# hotair.net
KiCad netlist of a schematic drawn in Altium Designer
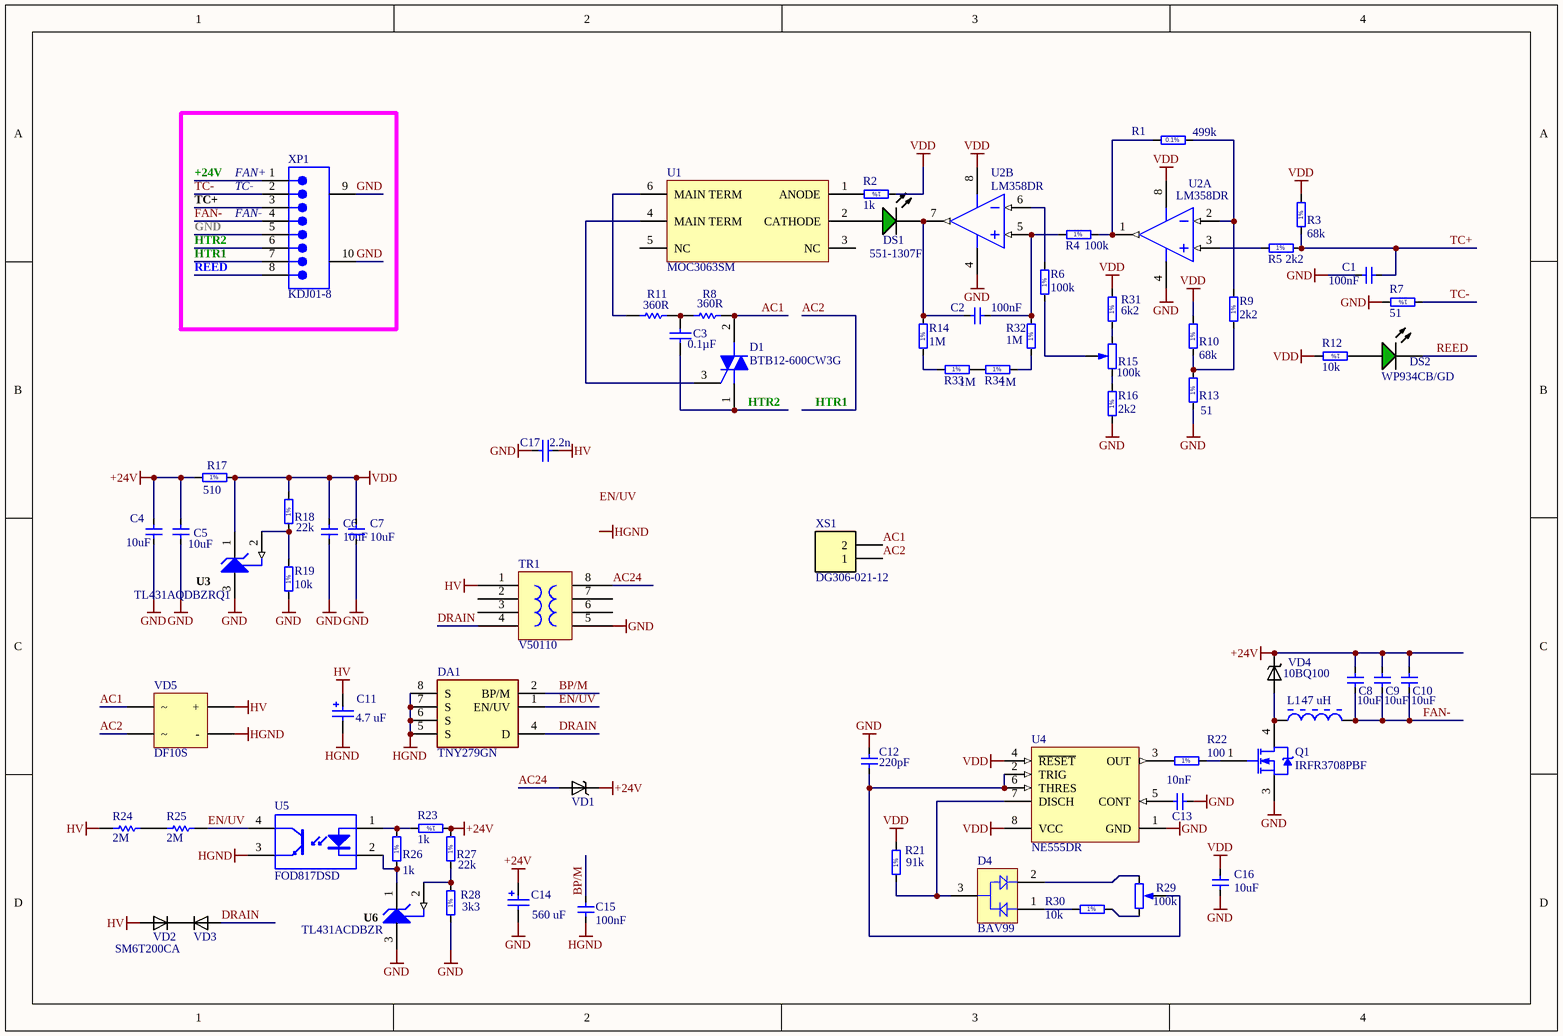
[diagram p0: hotair.SchDoc]

(export (version "E")
  (design (tool "Eeschema 10.0.6"))
  (components
    (comp (ref "C1")
      (value "100nF")
      (footprint "CAP0805R")
      (fields
        (field (name "PART NUMBER") "CC0805_100NF_50V_10%_X7R")
        (field (name "VOLTAGE") "50V")
        (field (name "TOLERANCE") "±10%")
        (field (name "AUTHOR") "I. Kuznetsov")
      )
      (libsource (lib "Capacitor") (part "CAP_NON_POLAR"))
    )
    (comp (ref "C2")
      (value "100nF")
      (footprint "CAP0805R")
      (fields
        (field (name "PART NUMBER") "CC0805_100NF_50V_10%_X7R")
        (field (name "VOLTAGE") "50V")
        (field (name "TOLERANCE") "±10%")
        (field (name "AUTHOR") "I. Kuznetsov")
      )
      (libsource (lib "Capacitor") (part "CAP_NON_POLAR"))
    )
    (comp (ref "C3")
      (value "A104M15X7RF5TAA")
      (footprint "CAPA55-380X260")
      (fields
        (field (name "MANUFACTURER") "Vishay")
        (field (name "CAPACITANCE") "0.1µF")
        (field (name "TOLERANCE") "±20%")
      )
      (libsource (lib "Altium Content Vault") (part "CAP-NP-2"))
    )
    (comp (ref "C4")
      (value "10uF")
      (footprint "CAP0805R")
      (fields
        (field (name "PART NUMBER") "CC0805_10UF_25V_10%_X5R")
        (field (name "VOLTAGE") "25V")
        (field (name "TOLERANCE") "±10%")
        (field (name "AUTHOR") "I. Kuznetsov")
      )
      (libsource (lib "Capacitor") (part "CAP_NON_POLAR"))
    )
    (comp (ref "C5")
      (value "10uF")
      (footprint "CAP0805R")
      (fields
        (field (name "PART NUMBER") "CC0805_10UF_25V_10%_X5R")
        (field (name "VOLTAGE") "25V")
        (field (name "TOLERANCE") "±10%")
        (field (name "AUTHOR") "I. Kuznetsov")
      )
      (libsource (lib "Capacitor") (part "CAP_NON_POLAR"))
    )
    (comp (ref "C6")
      (value "10uF")
      (footprint "CAP0805R")
      (fields
        (field (name "PART NUMBER") "CC0805_10UF_25V_10%_X5R")
        (field (name "VOLTAGE") "25V")
        (field (name "TOLERANCE") "±10%")
        (field (name "AUTHOR") "I. Kuznetsov")
      )
      (libsource (lib "Capacitor") (part "CAP_NON_POLAR"))
    )
    (comp (ref "C7")
      (value "10uF")
      (footprint "CAP0805R")
      (fields
        (field (name "PART NUMBER") "CC0805_10UF_25V_10%_X5R")
        (field (name "VOLTAGE") "25V")
        (field (name "TOLERANCE") "±10%")
        (field (name "AUTHOR") "I. Kuznetsov")
      )
      (libsource (lib "Capacitor") (part "CAP_NON_POLAR"))
    )
    (comp (ref "C8")
      (value "10uF")
      (footprint "CAP1206R")
      (fields
        (field (name "PART NUMBER") "CC1206_10UF_10V_10%_X7R")
        (field (name "VOLTAGE") "10V")
        (field (name "TOLERANCE") "±10%")
        (field (name "AUTHOR") "I. Kuznetsov")
      )
      (libsource (lib "Capacitor") (part "CAP_NON_POLAR"))
    )
    (comp (ref "C9")
      (value "10uF")
      (footprint "CAP1206R")
      (fields
        (field (name "PART NUMBER") "CC1206_10UF_10V_10%_X7R")
        (field (name "VOLTAGE") "10V")
        (field (name "TOLERANCE") "±10%")
        (field (name "AUTHOR") "I. Kuznetsov")
      )
      (libsource (lib "Capacitor") (part "CAP_NON_POLAR"))
    )
    (comp (ref "C10")
      (value "10uF")
      (footprint "CAP1206R")
      (fields
        (field (name "PART NUMBER") "CC1206_10UF_10V_10%_X7R")
        (field (name "VOLTAGE") "10V")
        (field (name "TOLERANCE") "±10%")
        (field (name "AUTHOR") "I. Kuznetsov")
      )
      (libsource (lib "Capacitor") (part "CAP_NON_POLAR"))
    )
    (comp (ref "C11")
      (value "4.7 uF")
      (footprint "WCAP-ATG8_8x11.5x3.5")
      (description "WCAP-ATG8 Aluminum Electrolytic Capacitors, 8x11.5mm, 400 Vdc, 4.7 uF")
      (fields
        (field (name "PART NUMBER") "860011374005")
        (field (name "Comment") "400 Vdc, 4.7 uF")
        (field (name "PUBLISHER") "Wurth Elektronik")
      )
      (libsource (lib "ALTIUM-WCAP-ATG8-rev17a") (part "860011374005"))
    )
    (comp (ref "C12")
      (value "220pF")
      (footprint "CAP0805R")
      (fields
        (field (name "PART NUMBER") "CC0805_220PF_50V_5%_NP0")
        (field (name "VOLTAGE") "50V")
        (field (name "TOLERANCE") "±5%")
        (field (name "AUTHOR") "I. Kuznetsov")
      )
      (libsource (lib "Capacitor") (part "CAP_NON_POLAR"))
    )
    (comp (ref "C13")
      (value "10nF")
      (footprint "CAP0805R")
      (fields
        (field (name "PART NUMBER") "CC0805_10NF_250V_10%_X7R")
        (field (name "VOLTAGE") "250V")
        (field (name "TOLERANCE") "±10%")
        (field (name "AUTHOR") "I. Kuznetsov")
      )
      (libsource (lib "Capacitor") (part "CAP_NON_POLAR"))
    )
    (comp (ref "C14")
      (value "560 uF")
      (footprint "WCAP-ATG8_8x11.5x3.5")
      (description "WCAP-ATG8 Aluminum Electrolytic Capacitors, 8x11.5mm, 10 Vdc, 560 uF")
      (fields
        (field (name "PART NUMBER") "860010274012")
        (field (name "Comment") "10 Vdc, 560 uF")
        (field (name "PUBLISHER") "Wurth Elektronik")
      )
      (libsource (lib "ALTIUM-WCAP-ATG8-rev17a") (part "860010274012"))
    )
    (comp (ref "C15")
      (value "100nF")
      (footprint "CAP0805R")
      (fields
        (field (name "PART NUMBER") "CC0805_100NF_50V_10%_X7R")
        (field (name "VOLTAGE") "50V")
        (field (name "TOLERANCE") "±10%")
        (field (name "AUTHOR") "I. Kuznetsov")
      )
      (libsource (lib "Capacitor") (part "CAP_NON_POLAR"))
    )
    (comp (ref "C16")
      (value "10uF")
      (footprint "CAP0805R")
      (fields
        (field (name "PART NUMBER") "CC0805_10UF_25V_10%_X5R")
        (field (name "VOLTAGE") "25V")
        (field (name "TOLERANCE") "±10%")
        (field (name "AUTHOR") "I. Kuznetsov")
      )
      (libsource (lib "Capacitor") (part "CAP_NON_POLAR"))
    )
    (comp (ref "C17")
      (value "2.2n")
      (footprint "CAP_Y")
      (description "Y Capacitor")
      (fields (field (name "VOLTAGE") "1000V") (field (name "PARTNUMBER") "Y Film Capacitor"))
      (libsource (lib "base32") (part "CAP_Y"))
    )
    (comp (ref "D1")
      (value "BTB12-600CW3G")
      (footprint "ONSC-TO-220-3-221A-07")
      (description "Triacs, Silicon Bidirectional Thyristor, 3-Pin TO-220, Pb-Free, Tube")
      (fields (field (name "MANUFACTURER") "On Semiconductor"))
      (libsource (lib "Altium Content Vault") (part "ONSC-TRIAC-MT1MT2G-3"))
    )
    (comp (ref "D4")
      (value "BAV99")
      (footprint "INF-SOT23_L")
      (description "Silicon Switching Diode, SOT23, Reel, Green")
      (fields (field (name "MANUFACTURER") "Infineon"))
      (libsource (lib "Altium Content Vault") (part "INF-D_A1K2C3-3"))
    )
    (comp (ref "DA1")
      (value "TNY279GN")
      (footprint "SMDIP8")
      (libsource (lib "IC And Semiconductor") (part "TNY27x"))
    )
    (comp (ref "DS1")
      (value "551-1307F")
      (footprint "DIAL-LED-551-2_V")
      (fields (field (name "MANUFACTURER") "Dialight"))
      (libsource (lib "Altium Content Vault") (part "LED_GREEN_A1K2-2"))
    )
    (comp (ref "DS2")
      (value "WP934CB/GD")
      (footprint "KING-WP934CBGD_V")
      (description "Right Angle LED Indicator, 62.5 mW, 25 mA, -40 to 85 degC, 2-Pin THD, RoHS, Bulk")
      (fields (field (name "MANUFACTURER") "Kingbright"))
      (libsource (lib "Altium Content Vault") (part "LED-GREEN-KA-2"))
    )
    (comp (ref "L1")
      (value "RFB0807-470L")
      (footprint "COIL-RFB0807-2_V")
      (fields
        (field (name "TOLERANCE") "+/- 10%")
        (field (name "INDUCTANCE") "47 uH")
        (field (name "MANUFACTURER") "Coilcraft")
      )
      (libsource (lib "Altium Content Vault") (part "COIL-IND-2A"))
    )
    (comp (ref "Q1")
      (value "IRFR3708PBF")
      (footprint "INTR-TO-252AA-3_M")
      (description "Mosfet N-Channel, 30 V, 61 A, -55 to 175 degC, 3-Pin DPAK, RoHS, Tube")
      (fields (field (name "MANUFACTURER") "International Rectifier"))
      (libsource (lib "Altium Content Vault") (part "NEMOS-GSD-3_B"))
    )
    (comp (ref "R1")
      (value "499k")
      (footprint "RES0805R")
      (fields
        (field (name "PART NUMBER") "R0805_499K_0.1%_0.125W_25PPM")
        (field (name "POWER") "0.125W")
        (field (name "TOLERANCE") "±0.1%")
        (field (name "AUTHOR") "CERN DEM JLC")
      )
      (libsource (lib "Resistor") (part "Resistor - 0.1%"))
    )
    (comp (ref "R2")
      (value "1k")
      (footprint "RES0805R")
      (fields
        (field (name "PART NUMBER") "R0805_1K_1%_0.125W_100PPM")
        (field (name "POWER") "0.125W")
        (field (name "TOLERANCE") "±1%")
        (field (name "AUTHOR") "CERN DEM JLC")
      )
      (libsource (lib "Resistor") (part "Resistor - 1%"))
    )
    (comp (ref "R3")
      (value "68k")
      (footprint "RES0805R")
      (fields
        (field (name "PART NUMBER") "R0805_68K_1%_0.125W_100PPM")
        (field (name "POWER") "0.125W")
        (field (name "TOLERANCE") "±1%")
        (field (name "AUTHOR") "CERN DEM JLC")
      )
      (libsource (lib "Resistor") (part "Resistor - 1%"))
    )
    (comp (ref "R4")
      (value "100k")
      (footprint "RES0805R")
      (fields
        (field (name "PART NUMBER") "R0805_100K_1%_0.125W_100PPM")
        (field (name "POWER") "0.125W")
        (field (name "TOLERANCE") "±1%")
        (field (name "AUTHOR") "CERN DEM JLC")
      )
      (libsource (lib "Resistor") (part "Resistor - 1%"))
    )
    (comp (ref "R5")
      (value "2k2")
      (footprint "RES0805R")
      (fields
        (field (name "PART NUMBER") "R0805_2K2_1%_0.125W_100PPM")
        (field (name "POWER") "0.125W")
        (field (name "TOLERANCE") "±1%")
        (field (name "AUTHOR") "CERN DEM JLC")
      )
      (libsource (lib "Resistor") (part "Resistor - 1%"))
    )
    (comp (ref "R6")
      (value "100k")
      (footprint "RES0805R")
      (fields
        (field (name "PART NUMBER") "R0805_100K_1%_0.125W_100PPM")
        (field (name "POWER") "0.125W")
        (field (name "TOLERANCE") "±1%")
        (field (name "AUTHOR") "CERN DEM JLC")
      )
      (libsource (lib "Resistor") (part "Resistor - 1%"))
    )
    (comp (ref "R7")
      (value "51")
      (footprint "RES0805R")
      (fields
        (field (name "PART NUMBER") "R0805_51R_1%_0.125W_100PPM")
        (field (name "POWER") "0.125W")
        (field (name "TOLERANCE") "±1%")
        (field (name "AUTHOR") "CERN DEM JLC")
      )
      (libsource (lib "Resistor") (part "Resistor - 1%"))
    )
    (comp (ref "R8")
      (value "360R")
      (footprint "RESC2010(5025)_L")
      (description "360R 0.75W 1% 2010 (5025 Metric)  SMD")
      (fields (field (name "POWER") "0.75 W") (field (name "TOLERANCE") "1 %"))
      (libsource (lib "Altium Content Vault") (part "RES"))
    )
    (comp (ref "R9")
      (value "2k2")
      (footprint "RES0805R")
      (fields
        (field (name "PART NUMBER") "R0805_2K2_1%_0.125W_100PPM")
        (field (name "POWER") "0.125W")
        (field (name "TOLERANCE") "±1%")
        (field (name "AUTHOR") "CERN DEM JLC")
      )
      (libsource (lib "Resistor") (part "Resistor - 1%"))
    )
    (comp (ref "R10")
      (value "68k")
      (footprint "RES0805R")
      (fields
        (field (name "PART NUMBER") "R0805_68K_1%_0.125W_100PPM")
        (field (name "POWER") "0.125W")
        (field (name "TOLERANCE") "±1%")
        (field (name "AUTHOR") "CERN DEM JLC")
      )
      (libsource (lib "Resistor") (part "Resistor - 1%"))
    )
    (comp (ref "R11")
      (value "360R")
      (footprint "RESC2010(5025)_L")
      (description "360R 0.75W 1% 2010 (5025 Metric)  SMD")
      (fields (field (name "POWER") "0.75 W") (field (name "TOLERANCE") "1 %"))
      (libsource (lib "Altium Content Vault") (part "RES"))
    )
    (comp (ref "R12")
      (value "10k")
      (footprint "RES0805R")
      (fields
        (field (name "PART NUMBER") "R0805_10K_1%_0.125W_100PPM")
        (field (name "POWER") "0.125W")
        (field (name "TOLERANCE") "±1%")
        (field (name "AUTHOR") "CERN DEM JLC")
      )
      (libsource (lib "Resistor") (part "Resistor - 1%"))
    )
    (comp (ref "R13")
      (value "51")
      (footprint "RES0805R")
      (fields
        (field (name "PART NUMBER") "R0805_51R_1%_0.125W_100PPM")
        (field (name "POWER") "0.125W")
        (field (name "TOLERANCE") "±1%")
        (field (name "AUTHOR") "CERN DEM JLC")
      )
      (libsource (lib "Resistor") (part "Resistor - 1%"))
    )
    (comp (ref "R14")
      (value "1M")
      (footprint "RES0805R")
      (fields
        (field (name "PART NUMBER") "R0805_1M_1%_0.125W_100PPM")
        (field (name "POWER") "0.125W")
        (field (name "TOLERANCE") "±1%")
        (field (name "AUTHOR") "CERN DEM JLC")
      )
      (libsource (lib "Resistor") (part "Resistor - 1%"))
    )
    (comp (ref "R15")
      (value "100k")
      (footprint "CA9MH")
      (fields (field (name "PART NUMBER") "CA9MH"))
      (libsource (lib "Resistor") (part "Resistor - Variable"))
    )
    (comp (ref "R16")
      (value "2k2")
      (footprint "RES0805R")
      (fields
        (field (name "PART NUMBER") "R0805_2K2_1%_0.125W_100PPM")
        (field (name "POWER") "0.125W")
        (field (name "TOLERANCE") "±1%")
        (field (name "AUTHOR") "CERN DEM JLC")
      )
      (libsource (lib "Resistor") (part "Resistor - 1%"))
    )
    (comp (ref "R17")
      (value "510")
      (footprint "RES0805R")
      (fields
        (field (name "PART NUMBER") "R0805_510R_1%_0.125W_100PPM")
        (field (name "POWER") "0.125W")
        (field (name "TOLERANCE") "±1%")
        (field (name "AUTHOR") "CERN DEM JLC")
      )
      (libsource (lib "Resistor") (part "Resistor - 1%"))
    )
    (comp (ref "R18")
      (value "22k")
      (footprint "RES0805R")
      (fields
        (field (name "PART NUMBER") "R0805_22K_1%_0.125W_100PPM")
        (field (name "POWER") "0.125W")
        (field (name "TOLERANCE") "±1%")
        (field (name "AUTHOR") "CERN DEM JLC")
      )
      (libsource (lib "Resistor") (part "Resistor - 1%"))
    )
    (comp (ref "R19")
      (value "10k")
      (footprint "RES0805R")
      (fields
        (field (name "PART NUMBER") "R0805_10K_1%_0.125W_100PPM")
        (field (name "POWER") "0.125W")
        (field (name "TOLERANCE") "±1%")
        (field (name "AUTHOR") "CERN DEM JLC")
      )
      (libsource (lib "Resistor") (part "Resistor - 1%"))
    )
    (comp (ref "R21")
      (value "91k")
      (footprint "RES0805R")
      (fields
        (field (name "PART NUMBER") "R0805_91K_1%_0.125W_100PPM")
        (field (name "POWER") "0.125W")
        (field (name "TOLERANCE") "±1%")
        (field (name "AUTHOR") "CERN DEM JLC")
      )
      (libsource (lib "Resistor") (part "Resistor - 1%"))
    )
    (comp (ref "R22")
      (value "100")
      (footprint "RES0805R")
      (fields
        (field (name "PART NUMBER") "R0805_100R_1%_0.125W_100PPM")
        (field (name "POWER") "0.125W")
        (field (name "TOLERANCE") "±1%")
        (field (name "AUTHOR") "CERN DEM JLC")
      )
      (libsource (lib "Resistor") (part "Resistor - 1%"))
    )
    (comp (ref "R23")
      (value "1k")
      (footprint "RES0805R")
      (fields
        (field (name "PART NUMBER") "R0805_1K_1%_0.125W_100PPM")
        (field (name "POWER") "0.125W")
        (field (name "TOLERANCE") "±1%")
        (field (name "AUTHOR") "CERN DEM JLC")
      )
      (libsource (lib "Resistor") (part "Resistor - 1%"))
    )
    (comp (ref "R24")
      (value "2M")
      (footprint "RESC1206(3216)_L")
      (description "2M 0.25W 5% 1206 (3216 Metric)  SMD")
      (fields (field (name "POWER") "0.25 W") (field (name "TOLERANCE") "5 %"))
      (libsource (lib "Altium Content Vault") (part "RES"))
    )
    (comp (ref "R25")
      (value "2M")
      (footprint "RESC1206(3216)_L")
      (description "2M 0.25W 5% 1206 (3216 Metric)  SMD")
      (fields (field (name "POWER") "0.25 W") (field (name "TOLERANCE") "5 %"))
      (libsource (lib "Altium Content Vault") (part "RES"))
    )
    (comp (ref "R26")
      (value "1k")
      (footprint "RES0805R")
      (fields
        (field (name "PART NUMBER") "R0805_1K_1%_0.125W_100PPM")
        (field (name "POWER") "0.125W")
        (field (name "TOLERANCE") "±1%")
        (field (name "AUTHOR") "CERN DEM JLC")
      )
      (libsource (lib "Resistor") (part "Resistor - 1%"))
    )
    (comp (ref "R27")
      (value "22k")
      (footprint "RES0805R")
      (fields
        (field (name "PART NUMBER") "R0805_22K_1%_0.125W_100PPM")
        (field (name "POWER") "0.125W")
        (field (name "TOLERANCE") "±1%")
        (field (name "AUTHOR") "CERN DEM JLC")
      )
      (libsource (lib "Resistor") (part "Resistor - 1%"))
    )
    (comp (ref "R28")
      (value "3k3")
      (footprint "RES0805R")
      (fields
        (field (name "PART NUMBER") "R0805_3K3_1%_0.125W_100PPM")
        (field (name "POWER") "0.125W")
        (field (name "TOLERANCE") "±1%")
        (field (name "AUTHOR") "CERN DEM JLC")
      )
      (libsource (lib "Resistor") (part "Resistor - 1%"))
    )
    (comp (ref "R29")
      (value "100k")
      (footprint "CA9MH")
      (fields (field (name "PART NUMBER") "CA9MH"))
      (libsource (lib "Resistor") (part "Resistor - Variable"))
    )
    (comp (ref "R30")
      (value "10k")
      (footprint "RES0805R")
      (fields
        (field (name "PART NUMBER") "R0805_10K_1%_0.125W_100PPM")
        (field (name "POWER") "0.125W")
        (field (name "TOLERANCE") "±1%")
        (field (name "AUTHOR") "CERN DEM JLC")
      )
      (libsource (lib "Resistor") (part "Resistor - 1%"))
    )
    (comp (ref "R31")
      (value "6k2")
      (footprint "RES0805R")
      (fields
        (field (name "PART NUMBER") "R0805_6K2_1%_0.125W_100PPM")
        (field (name "POWER") "0.125W")
        (field (name "TOLERANCE") "±1%")
        (field (name "AUTHOR") "CERN DEM JLC")
      )
      (libsource (lib "Resistor") (part "Resistor - 1%"))
    )
    (comp (ref "R32")
      (value "1M")
      (footprint "RES0805R")
      (fields
        (field (name "PART NUMBER") "R0805_1M_1%_0.125W_100PPM")
        (field (name "POWER") "0.125W")
        (field (name "TOLERANCE") "±1%")
        (field (name "AUTHOR") "CERN DEM JLC")
      )
      (libsource (lib "Resistor") (part "Resistor - 1%"))
    )
    (comp (ref "R33")
      (value "1M")
      (footprint "RES0805R")
      (fields
        (field (name "PART NUMBER") "R0805_1M_1%_0.125W_100PPM")
        (field (name "POWER") "0.125W")
        (field (name "TOLERANCE") "±1%")
        (field (name "AUTHOR") "CERN DEM JLC")
      )
      (libsource (lib "Resistor") (part "Resistor - 1%"))
    )
    (comp (ref "R34")
      (value "1M")
      (footprint "RES0805R")
      (fields
        (field (name "PART NUMBER") "R0805_1M_1%_0.125W_100PPM")
        (field (name "POWER") "0.125W")
        (field (name "TOLERANCE") "±1%")
        (field (name "AUTHOR") "CERN DEM JLC")
      )
      (libsource (lib "Resistor") (part "Resistor - 1%"))
    )
    (comp (ref "TR1") (value "V50110") (footprint "V50110") (libsource (lib "*") (part "V50110")))
    (comp (ref "U1")
      (value "MOC3063SM")
      (footprint "FAIR-MDIP 6L-N06C_V")
      (fields (field (name "GENERIC PART NUMBER") "MOC3063"))
      (libsource (lib "Altium Content Vault") (part "FAIR-MOC3063SM-6"))
    )
    (comp (ref "U2")
      (value "LM358DR")
      (footprint "D0008A_L")
      (libsource (lib "Altium Content Vault") (part "TI-LM358-8"))
    )
    (comp (ref "U3")
      (value "TL431AQDBZRQ1")
      (footprint "DBZ0003A_M")
      (fields (field (name "MANUFACTURER") "Texas Instruments"))
      (libsource (lib "Altium Content Vault") (part "TI-TL431A-Q1DBZ3"))
    )
    (comp (ref "U4")
      (value "NE555DR")
      (footprint "D0008A_M")
      (libsource (lib "Altium Content Vault") (part "TI-NE555-P8"))
    )
    (comp (ref "U5")
      (value "FOD817DSD")
      (footprint "FAIR-MDIP-4_V")
      (fields (field (name "MANUFACTURER") "Fairchild Semiconductor"))
      (libsource (lib "Altium Content Vault") (part "OPTO-AKEC-4"))
    )
    (comp (ref "U6")
      (value "TL431ACDBZR")
      (footprint "DBZ0003A_L")
      (fields (field (name "MANUFACTURER") "Texas Instruments"))
      (libsource (lib "Altium Content Vault") (part "TI-TL431ADBZ3"))
    )
    (comp (ref "VD1")
      (value "10BQ100")
      (footprint "DO-214AA")
      (libsource (lib "IC And Semiconductor") (part "Diode - Schottky"))
    )
    (comp (ref "VD2")
      (value "SM6T200CA")
      (footprint "SMB")
      (libsource (lib "IC And Semiconductor") (part "Diode - General"))
    )
    (comp (ref "VD3")
      (value "US1M")
      (footprint "SMA")
      (libsource (lib "IC And Semiconductor") (part "Diode - General"))
    )
    (comp (ref "VD4")
      (value "10BQ100")
      (footprint "DO-214AA")
      (libsource (lib "IC And Semiconductor") (part "Diode - Schottky"))
    )
    (comp (ref "VD5")
      (value "DF10S")
      (footprint "DF-S")
      (fields (field (name "PARTNUMBER") "DF10S"))
      (libsource (lib "base32") (part "DF10S"))
    )
    (comp (ref "XP1") (value "KDJ01-8") (footprint "KDJ01-8") (libsource (lib "Connector") (part "KDJ01-8")))
    (comp (ref "XS1")
      (value "DG306-021-12")
      (footprint "DG306")
      (fields (field (name "PARTNUMBER") "DG306-021-12"))
      (libsource (lib "base32") (part "DG306-021-12"))
    )
  )
  (nets
    (net (code "1") (name "+24V") (class "Default")
      (node (ref "C10") (pin "2") (pinfunction "2_2") (pintype "passive"))
      (node (ref "C14") (pin "1") (pinfunction "P_1") (pintype "passive"))
      (node (ref "C4") (pin "2") (pinfunction "2_2") (pintype "passive"))
      (node (ref "C5") (pin "2") (pinfunction "2_2") (pintype "passive"))
      (node (ref "C8") (pin "2") (pinfunction "2_2") (pintype "passive"))
      (node (ref "C9") (pin "2") (pinfunction "2_2") (pintype "passive"))
      (node (ref "R17") (pin "1") (pinfunction "1_1") (pintype "passive"))
      (node (ref "R23") (pin "1") (pinfunction "1_1") (pintype "passive"))
      (node (ref "R27") (pin "2") (pinfunction "2_2") (pintype "passive"))
      (node (ref "VD1") (pin "K") (pinfunction "K_K") (pintype "passive"))
      (node (ref "VD4") (pin "K") (pinfunction "K_K") (pintype "passive"))
      (node (ref "XP1") (pin "1") (pinfunction "1_1") (pintype "passive"))
    )
    (net (code "2") (name "/AC1") (class "Default")
      (node (ref "D1") (pin "2") (pinfunction "MT2_2") (pintype "passive"))
      (node (ref "R8") (pin "2") (pinfunction "2_2") (pintype "passive"))
      (node (ref "VD5") (pin "4") (pinfunction "~_4") (pintype "passive"))
      (node (ref "XS1") (pin "2") (pinfunction "2_2") (pintype "passive"))
    )
    (net (code "3") (name "/AC2") (class "Default")
      (node (ref "VD5") (pin "3") (pinfunction "~_3") (pintype "passive"))
      (node (ref "XP1") (pin "7") (pinfunction "7_7") (pintype "passive"))
      (node (ref "XS1") (pin "1") (pinfunction "1_1") (pintype "passive"))
    )
    (net (code "4") (name "/AC24") (class "Default")
      (node (ref "TR1") (pin "8") (pinfunction "8_8") (pintype "passive"))
      (node (ref "VD1") (pin "A") (pinfunction "A_A") (pintype "passive"))
    )
    (net (code "5") (name "/BP{slash}M") (class "Default")
      (node (ref "C15") (pin "2") (pinfunction "2_2") (pintype "passive"))
      (node (ref "DA1") (pin "2") (pinfunction "BP/M_2") (pintype "passive"))
    )
    (net (code "6") (name "/DRAIN") (class "Default")
      (node (ref "DA1") (pin "4") (pinfunction "D_4") (pintype "passive"))
      (node (ref "TR1") (pin "4") (pinfunction "4_4") (pintype "passive"))
      (node (ref "VD3") (pin "A") (pinfunction "A_A") (pintype "passive"))
    )
    (net (code "7") (name "/EN{slash}UV") (class "Default")
      (node (ref "DA1") (pin "1") (pinfunction "EN/UV_1") (pintype "passive"))
      (node (ref "R25") (pin "2") (pinfunction "2_2") (pintype "passive"))
      (node (ref "U5") (pin "4") (pinfunction "COLLECTOR_4") (pintype "passive"))
    )
    (net (code "8") (name "/FAN-") (class "Default")
      (node (ref "C10") (pin "1") (pinfunction "1_1") (pintype "passive"))
      (node (ref "C8") (pin "1") (pinfunction "1_1") (pintype "passive"))
      (node (ref "C9") (pin "1") (pinfunction "1_1") (pintype "passive"))
      (node (ref "L1") (pin "2") (pinfunction "2_2") (pintype "passive"))
      (node (ref "XP1") (pin "4") (pinfunction "4_4") (pintype "passive"))
    )
    (net (code "9") (name "/HTR2") (class "Default")
      (node (ref "C3") (pin "1") (pinfunction "1_1") (pintype "passive"))
      (node (ref "D1") (pin "1") (pinfunction "MT1_1") (pintype "passive"))
      (node (ref "XP1") (pin "6") (pinfunction "6_6") (pintype "passive"))
    )
    (net (code "10") (name "/REED") (class "Default")
      (node (ref "DS2") (pin "1") (pinfunction "K_1") (pintype "passive"))
      (node (ref "XP1") (pin "8") (pinfunction "8_8") (pintype "passive"))
    )
    (net (code "11") (name "/TC+") (class "Default")
      (node (ref "C1") (pin "2") (pinfunction "2_2") (pintype "passive"))
      (node (ref "R3") (pin "1") (pinfunction "1_1") (pintype "passive"))
      (node (ref "R5") (pin "2") (pinfunction "2_2") (pintype "passive"))
      (node (ref "XP1") (pin "3") (pinfunction "3_3") (pintype "passive"))
    )
    (net (code "12") (name "/TC-") (class "Default")
      (node (ref "R7") (pin "1") (pinfunction "1_1") (pintype "passive"))
      (node (ref "XP1") (pin "2") (pinfunction "2_2") (pintype "passive"))
    )
    (net (code "13") (name "GND") (class "Default")
      (node (ref "C1") (pin "1") (pinfunction "1_1") (pintype "passive"))
      (node (ref "C12") (pin "2") (pinfunction "2_2") (pintype "passive"))
      (node (ref "C13") (pin "2") (pinfunction "2_2") (pintype "passive"))
      (node (ref "C14") (pin "2") (pinfunction "N_2") (pintype "passive"))
      (node (ref "C16") (pin "1") (pinfunction "1_1") (pintype "passive"))
      (node (ref "C17") (pin "1") (pinfunction "1_1") (pintype "passive"))
      (node (ref "C4") (pin "1") (pinfunction "1_1") (pintype "passive"))
      (node (ref "C5") (pin "1") (pinfunction "1_1") (pintype "passive"))
      (node (ref "C6") (pin "1") (pinfunction "1_1") (pintype "passive"))
      (node (ref "C7") (pin "1") (pinfunction "1_1") (pintype "passive"))
      (node (ref "Q1") (pin "3") (pinfunction "S_3") (pintype "passive"))
      (node (ref "R13") (pin "1") (pinfunction "1_1") (pintype "passive"))
      (node (ref "R16") (pin "1") (pinfunction "1_1") (pintype "passive"))
      (node (ref "R19") (pin "1") (pinfunction "1_1") (pintype "passive"))
      (node (ref "R28") (pin "1") (pinfunction "1_1") (pintype "passive"))
      (node (ref "R7") (pin "2") (pinfunction "2_2") (pintype "passive"))
      (node (ref "TR1") (pin "5") (pinfunction "5_5") (pintype "passive"))
      (node (ref "U2") (pin "4") (pinfunction "GND_4") (pintype "power_in"))
      (node (ref "U3") (pin "3") (pinfunction "ANODE_3") (pintype "power_in"))
      (node (ref "U4") (pin "1") (pinfunction "GND_1") (pintype "power_in"))
      (node (ref "U6") (pin "3") (pinfunction "ANODE_3") (pintype "passive"))
      (node (ref "XP1") (pin "10") (pinfunction "10_10") (pintype "passive"))
      (node (ref "XP1") (pin "5") (pinfunction "5_5") (pintype "passive"))
      (node (ref "XP1") (pin "9") (pinfunction "9_9") (pintype "passive"))
    )
    (net (code "14") (name "HGND") (class "Default")
      (node (ref "C11") (pin "2") (pinfunction "N_2") (pintype "passive"))
      (node (ref "C15") (pin "1") (pinfunction "1_1") (pintype "passive"))
      (node (ref "DA1") (pin "5") (pinfunction "S_5") (pintype "passive"))
      (node (ref "DA1") (pin "6") (pinfunction "S_6") (pintype "passive"))
      (node (ref "DA1") (pin "7") (pinfunction "S_7") (pintype "passive"))
      (node (ref "DA1") (pin "8") (pinfunction "S_8") (pintype "passive"))
      (node (ref "U5") (pin "3") (pinfunction "EMITTER_3") (pintype "passive"))
      (node (ref "VD5") (pin "2") (pinfunction "-_2") (pintype "passive"))
    )
    (net (code "15") (name "HV") (class "Default")
      (node (ref "C11") (pin "1") (pinfunction "P_1") (pintype "passive"))
      (node (ref "C17") (pin "2") (pinfunction "2_2") (pintype "passive"))
      (node (ref "R24") (pin "1") (pinfunction "1_1") (pintype "passive"))
      (node (ref "TR1") (pin "1") (pinfunction "1_1") (pintype "passive"))
      (node (ref "VD2") (pin "A") (pinfunction "A_A") (pintype "passive"))
      (node (ref "VD5") (pin "1") (pinfunction "+_1") (pintype "passive"))
    )
    (net (code "16") (name "Net-(C3-Pad2)") (class "Default")
      (node (ref "C3") (pin "2") (pinfunction "2_2") (pintype "passive"))
      (node (ref "R11") (pin "2") (pinfunction "2_2") (pintype "passive"))
      (node (ref "R8") (pin "1") (pinfunction "1_1") (pintype "passive"))
    )
    (net (code "17") (name "Net-(D1-G)") (class "Default")
      (node (ref "D1") (pin "3") (pinfunction "G_3") (pintype "passive"))
      (node (ref "U1") (pin "4") (pinfunction "MAIN_TERM_4") (pintype "passive"))
    )
    (net (code "18") (name "Net-(D4-A1)") (class "Default")
      (node (ref "D4") (pin "1") (pinfunction "A1_1") (pintype "passive"))
      (node (ref "R30") (pin "1") (pinfunction "1_1") (pintype "passive"))
    )
    (net (code "19") (name "Net-(D4-C)") (class "Default")
      (node (ref "D4") (pin "3") (pinfunction "C_3") (pintype "passive"))
      (node (ref "R21") (pin "1") (pinfunction "1_1") (pintype "passive"))
      (node (ref "U4") (pin "7") (pinfunction "DISCH_7") (pintype "open_collector"))
    )
    (net (code "20") (name "Net-(D4-K2)") (class "Default")
      (node (ref "D4") (pin "2") (pinfunction "K2_2") (pintype "passive"))
      (node (ref "R29") (pin "1") (pinfunction "1_1") (pintype "passive"))
    )
    (net (code "21") (name "Net-(DS1-A)") (class "Default")
      (node (ref "DS1") (pin "1") (pinfunction "A_1") (pintype "passive"))
      (node (ref "U1") (pin "2") (pinfunction "CATHODE_2") (pintype "passive"))
    )
    (net (code "22") (name "Net-(DS1-K)") (class "Default")
      (node (ref "C2") (pin "1") (pinfunction "1_1") (pintype "passive"))
      (node (ref "DS1") (pin "2") (pinfunction "K_2") (pintype "passive"))
      (node (ref "R14") (pin "2") (pinfunction "2_2") (pintype "passive"))
      (node (ref "U2") (pin "7") (pinfunction "2OUT_7") (pintype "output"))
    )
    (net (code "23") (name "Net-(DS2-A)") (class "Default")
      (node (ref "DS2") (pin "2") (pinfunction "A_2") (pintype "passive"))
      (node (ref "R12") (pin "1") (pinfunction "1_1") (pintype "passive"))
    )
    (net (code "24") (name "Net-(Q1-D)") (class "Default")
      (node (ref "L1") (pin "1") (pinfunction "1_1") (pintype "passive"))
      (node (ref "Q1") (pin "4") (pinfunction "D_4") (pintype "passive"))
      (node (ref "VD4") (pin "A") (pinfunction "A_A") (pintype "passive"))
    )
    (net (code "25") (name "Net-(Q1-G)") (class "Default")
      (node (ref "Q1") (pin "1") (pinfunction "G_1") (pintype "passive"))
      (node (ref "R22") (pin "2") (pinfunction "2_2") (pintype "passive"))
    )
    (net (code "26") (name "Net-(R10-Pad1)") (class "Default")
      (node (ref "R10") (pin "1") (pinfunction "1_1") (pintype "passive"))
      (node (ref "R13") (pin "2") (pinfunction "2_2") (pintype "passive"))
      (node (ref "R9") (pin "1") (pinfunction "1_1") (pintype "passive"))
    )
    (net (code "27") (name "Net-(R11-Pad1)") (class "Default")
      (node (ref "R11") (pin "1") (pinfunction "1_1") (pintype "passive"))
      (node (ref "U1") (pin "6") (pinfunction "MAIN_TERM_6") (pintype "passive"))
    )
    (net (code "28") (name "Net-(R14-Pad1)") (class "Default")
      (node (ref "R14") (pin "1") (pinfunction "1_1") (pintype "passive"))
      (node (ref "R33") (pin "1") (pinfunction "1_1") (pintype "passive"))
    )
    (net (code "29") (name "Net-(R15-Pad1)") (class "Default")
      (node (ref "R15") (pin "1") (pinfunction "1_1") (pintype "passive"))
      (node (ref "R31") (pin "1") (pinfunction "1_1") (pintype "passive"))
    )
    (net (code "30") (name "Net-(R15-Pad2)") (class "Default")
      (node (ref "R15") (pin "2") (pinfunction "2_2") (pintype "passive"))
      (node (ref "R6") (pin "1") (pinfunction "1_1") (pintype "passive"))
    )
    (net (code "31") (name "Net-(R15-Pad3)") (class "Default")
      (node (ref "R15") (pin "3") (pinfunction "3_3") (pintype "passive"))
      (node (ref "R16") (pin "2") (pinfunction "2_2") (pintype "passive"))
    )
    (net (code "32") (name "Net-(R24-Pad2)") (class "Default")
      (node (ref "R24") (pin "2") (pinfunction "2_2") (pintype "passive"))
      (node (ref "R25") (pin "1") (pinfunction "1_1") (pintype "passive"))
    )
    (net (code "33") (name "Net-(R29-Pad3)") (class "Default")
      (node (ref "R29") (pin "3") (pinfunction "3_3") (pintype "passive"))
      (node (ref "R30") (pin "2") (pinfunction "2_2") (pintype "passive"))
    )
    (net (code "34") (name "Net-(R32-Pad1)") (class "Default")
      (node (ref "R32") (pin "1") (pinfunction "1_1") (pintype "passive"))
      (node (ref "R34") (pin "2") (pinfunction "2_2") (pintype "passive"))
    )
    (net (code "35") (name "Net-(R33-Pad2)") (class "Default")
      (node (ref "R33") (pin "2") (pinfunction "2_2") (pintype "passive"))
      (node (ref "R34") (pin "1") (pinfunction "1_1") (pintype "passive"))
    )
    (net (code "36") (name "Net-(U1-ANODE)") (class "Default")
      (node (ref "R2") (pin "2") (pinfunction "2_2") (pintype "passive"))
      (node (ref "U1") (pin "1") (pinfunction "ANODE_1") (pintype "passive"))
    )
    (net (code "37") (name "Net-(U2A-1IN+)") (class "Default")
      (node (ref "R5") (pin "1") (pinfunction "1_1") (pintype "passive"))
      (node (ref "U2") (pin "3") (pinfunction "1IN+_3") (pintype "input"))
    )
    (net (code "38") (name "Net-(U2A-1IN-)") (class "Default")
      (node (ref "R1") (pin "2") (pinfunction "2_2") (pintype "passive"))
      (node (ref "R9") (pin "2") (pinfunction "2_2") (pintype "passive"))
      (node (ref "U2") (pin "2") (pinfunction "1IN-_2") (pintype "input"))
    )
    (net (code "39") (name "Net-(U2A-1OUT)") (class "Default")
      (node (ref "R1") (pin "1") (pinfunction "1_1") (pintype "passive"))
      (node (ref "R4") (pin "2") (pinfunction "2_2") (pintype "passive"))
      (node (ref "U2") (pin "1") (pinfunction "1OUT_1") (pintype "output"))
    )
    (net (code "40") (name "Net-(U2B-2IN+)") (class "Default")
      (node (ref "C2") (pin "2") (pinfunction "2_2") (pintype "passive"))
      (node (ref "R32") (pin "2") (pinfunction "2_2") (pintype "passive"))
      (node (ref "R4") (pin "1") (pinfunction "1_1") (pintype "passive"))
      (node (ref "U2") (pin "5") (pinfunction "2IN+_5") (pintype "input"))
    )
    (net (code "41") (name "Net-(U2B-2IN-)") (class "Default")
      (node (ref "R6") (pin "2") (pinfunction "2_2") (pintype "passive"))
      (node (ref "U2") (pin "6") (pinfunction "2IN-_6") (pintype "input"))
    )
    (net (code "42") (name "Net-(U3-REF)") (class "Default")
      (node (ref "R18") (pin "1") (pinfunction "1_1") (pintype "passive"))
      (node (ref "R19") (pin "2") (pinfunction "2_2") (pintype "passive"))
      (node (ref "U3") (pin "2") (pinfunction "REF_2") (pintype "input"))
    )
    (net (code "43") (name "Net-(U4-CONT)") (class "Default")
      (node (ref "C13") (pin "1") (pinfunction "1_1") (pintype "passive"))
      (node (ref "U4") (pin "5") (pinfunction "CONT_5") (pintype "input"))
    )
    (net (code "44") (name "Net-(U4-OUT)") (class "Default")
      (node (ref "R22") (pin "1") (pinfunction "1_1") (pintype "passive"))
      (node (ref "U4") (pin "3") (pinfunction "OUT_3") (pintype "output"))
    )
    (net (code "45") (name "Net-(U4-THRES)") (class "Default")
      (node (ref "C12") (pin "1") (pinfunction "1_1") (pintype "passive"))
      (node (ref "R29") (pin "2") (pinfunction "2_2") (pintype "passive"))
      (node (ref "U4") (pin "2") (pinfunction "TRIG_2") (pintype "input"))
      (node (ref "U4") (pin "6") (pinfunction "THRES_6") (pintype "input"))
    )
    (net (code "46") (name "Net-(U5-ANODE)") (class "Default")
      (node (ref "R23") (pin "2") (pinfunction "2_2") (pintype "passive"))
      (node (ref "R26") (pin "2") (pinfunction "2_2") (pintype "passive"))
      (node (ref "U5") (pin "1") (pinfunction "ANODE_1") (pintype "passive"))
    )
    (net (code "47") (name "Net-(U5-CATHODE)") (class "Default")
      (node (ref "R26") (pin "1") (pinfunction "1_1") (pintype "passive"))
      (node (ref "U5") (pin "2") (pinfunction "CATHODE_2") (pintype "passive"))
      (node (ref "U6") (pin "1") (pinfunction "CATHODE_1") (pintype "passive"))
    )
    (net (code "48") (name "Net-(U6-REF)") (class "Default")
      (node (ref "R27") (pin "1") (pinfunction "1_1") (pintype "passive"))
      (node (ref "R28") (pin "2") (pinfunction "2_2") (pintype "passive"))
      (node (ref "U6") (pin "2") (pinfunction "REF_2") (pintype "input"))
    )
    (net (code "49") (name "Net-(VD2-PadK)") (class "Default")
      (node (ref "VD2") (pin "K") (pinfunction "K_K") (pintype "passive"))
      (node (ref "VD3") (pin "K") (pinfunction "K_K") (pintype "passive"))
    )
    (net (code "50") (name "VDD") (class "Default")
      (node (ref "C16") (pin "2") (pinfunction "2_2") (pintype "passive"))
      (node (ref "C6") (pin "2") (pinfunction "2_2") (pintype "passive"))
      (node (ref "C7") (pin "2") (pinfunction "2_2") (pintype "passive"))
      (node (ref "R10") (pin "2") (pinfunction "2_2") (pintype "passive"))
      (node (ref "R12") (pin "2") (pinfunction "2_2") (pintype "passive"))
      (node (ref "R17") (pin "2") (pinfunction "2_2") (pintype "passive"))
      (node (ref "R18") (pin "2") (pinfunction "2_2") (pintype "passive"))
      (node (ref "R2") (pin "1") (pinfunction "1_1") (pintype "passive"))
      (node (ref "R21") (pin "2") (pinfunction "2_2") (pintype "passive"))
      (node (ref "R3") (pin "2") (pinfunction "2_2") (pintype "passive"))
      (node (ref "R31") (pin "2") (pinfunction "2_2") (pintype "passive"))
      (node (ref "U2") (pin "8") (pinfunction "VCC_8") (pintype "power_in"))
      (node (ref "U3") (pin "1") (pinfunction "CATHODE_1") (pintype "passive"))
      (node (ref "U4") (pin "4") (pinfunction "~{RESET}_4") (pintype "input"))
      (node (ref "U4") (pin "8") (pinfunction "VCC_8") (pintype "power_in"))
    )
    (net (code "51") (name "unconnected-(TR1-Pad2)") (class "Default")
      (node (ref "TR1") (pin "2") (pinfunction "2_2") (pintype "passive"))
    )
    (net (code "52") (name "unconnected-(TR1-Pad3)") (class "Default")
      (node (ref "TR1") (pin "3") (pinfunction "3_3") (pintype "passive"))
    )
    (net (code "53") (name "unconnected-(TR1-Pad6)") (class "Default")
      (node (ref "TR1") (pin "6") (pinfunction "6_6") (pintype "passive"))
    )
    (net (code "54") (name "unconnected-(TR1-Pad7)") (class "Default")
      (node (ref "TR1") (pin "7") (pinfunction "7_7") (pintype "passive"))
    )
    (net (code "55") (name "unconnected-(U1-NC-Pad3)") (class "Default")
      (node (ref "U1") (pin "3") (pinfunction "NC_3") (pintype "passive"))
    )
    (net (code "56") (name "unconnected-(U1-NC-Pad5)") (class "Default")
      (node (ref "U1") (pin "5") (pinfunction "NC_5") (pintype "passive"))
    )
  )
)
